# LSU_4_9_OpenAFR_Gauge.net
KiCad netlist of a schematic drawn in EAGLE
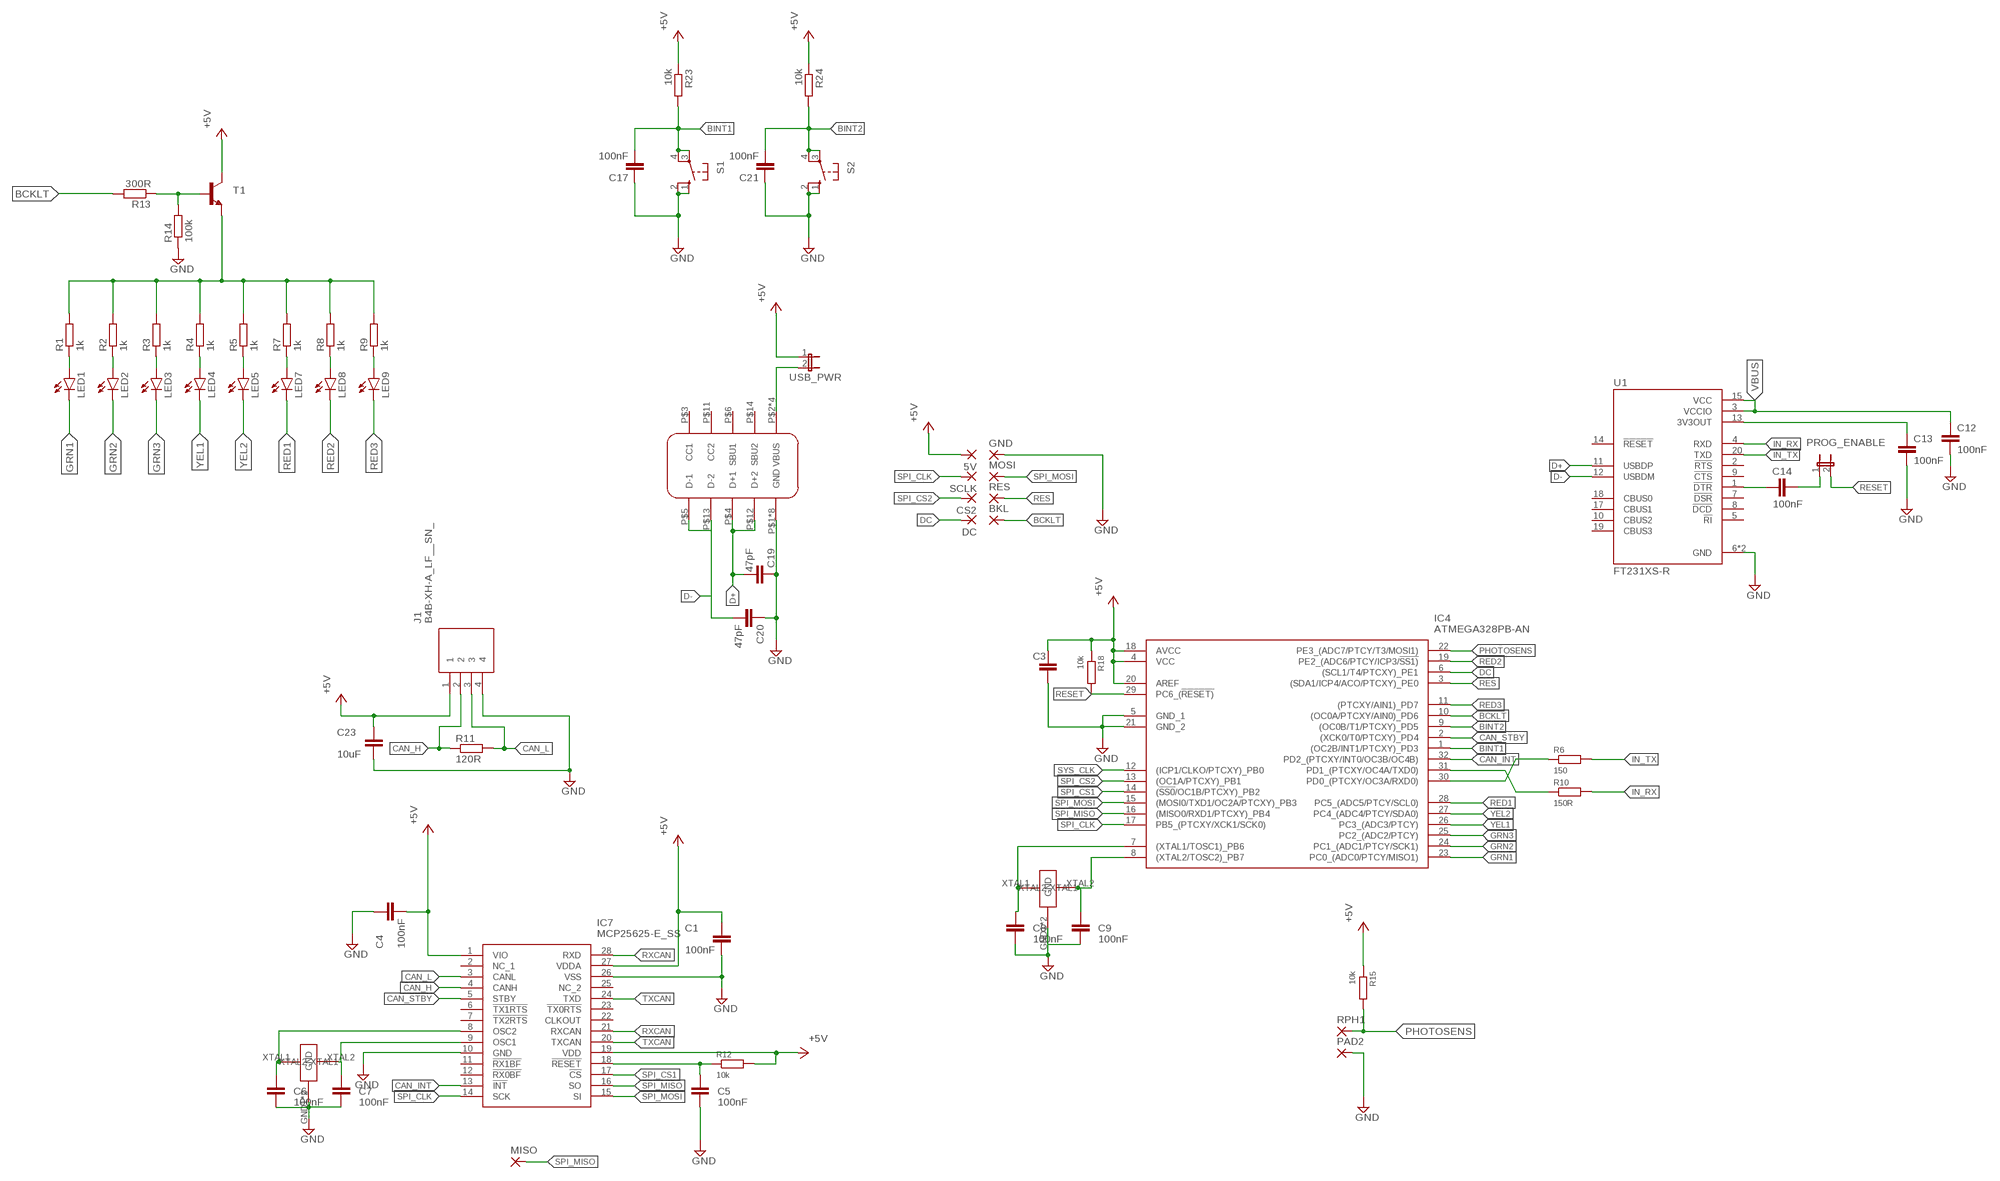
[diagram p0: schematic, sheet 1]

(export (version "E")
  (design (tool "Eeschema 10.0.6"))
  (components
    (comp (ref "5V")
      (value "1,6/0,9")
      (footprint "eagle-import:1,6_0,9")
      (libsource (lib "eagle-import") (part "1,6/0,9"))
    )
    (comp (ref "BKL")
      (value "1,6/0,9")
      (footprint "eagle-import:1,6_0,9")
      (libsource (lib "eagle-import") (part "1,6/0,9"))
    )
    (comp (ref "C1")
      (value "100nF")
      (footprint "eagle-import:C0805")
      (libsource (lib "eagle-import") (part "C-EUC0805"))
    )
    (comp (ref "C3")
      (value "100nF")
      (footprint "eagle-import:C0805")
      (libsource (lib "eagle-import") (part "C-EUC0805"))
    )
    (comp (ref "C4")
      (value "100nF")
      (footprint "eagle-import:C0805")
      (libsource (lib "eagle-import") (part "C-EUC0805"))
    )
    (comp (ref "C5")
      (value "100nF")
      (footprint "eagle-import:C0805")
      (libsource (lib "eagle-import") (part "C-EUC0805"))
    )
    (comp (ref "C6")
      (value "100nF")
      (footprint "eagle-import:C0805")
      (libsource (lib "eagle-import") (part "C-EUC0805"))
    )
    (comp (ref "C7")
      (value "100nF")
      (footprint "eagle-import:C0805")
      (libsource (lib "eagle-import") (part "C-EUC0805"))
    )
    (comp (ref "C8")
      (value "100nF")
      (footprint "eagle-import:C0805")
      (libsource (lib "eagle-import") (part "C-EUC0805"))
    )
    (comp (ref "C9")
      (value "100nF")
      (footprint "eagle-import:C0805")
      (libsource (lib "eagle-import") (part "C-EUC0805"))
    )
    (comp (ref "C12")
      (value "100nF")
      (footprint "eagle-import:C0805")
      (libsource (lib "eagle-import") (part "C-EUC0805"))
    )
    (comp (ref "C13")
      (value "100nF")
      (footprint "eagle-import:C0805")
      (libsource (lib "eagle-import") (part "C-EUC0805"))
    )
    (comp (ref "C14")
      (value "100nF")
      (footprint "eagle-import:C0805")
      (libsource (lib "eagle-import") (part "C-EUC0805"))
    )
    (comp (ref "C17")
      (value "100nF")
      (footprint "eagle-import:C0805")
      (libsource (lib "eagle-import") (part "C-EUC0805"))
    )
    (comp (ref "C19")
      (value "47pF")
      (footprint "eagle-import:C0805")
      (libsource (lib "eagle-import") (part "C-EUC0805"))
    )
    (comp (ref "C20")
      (value "47pF")
      (footprint "eagle-import:C0805")
      (libsource (lib "eagle-import") (part "C-EUC0805"))
    )
    (comp (ref "C21")
      (value "100nF")
      (footprint "eagle-import:C0805")
      (libsource (lib "eagle-import") (part "C-EUC0805"))
    )
    (comp (ref "C23")
      (value "10uF")
      (footprint "eagle-import:C0805")
      (libsource (lib "eagle-import") (part "C-EUC0805"))
    )
    (comp (ref "CS2")
      (value "1,6/0,9")
      (footprint "eagle-import:1,6_0,9")
      (libsource (lib "eagle-import") (part "1,6/0,9"))
    )
    (comp (ref "DC")
      (value "1,6/0,9")
      (footprint "eagle-import:1,6_0,9")
      (libsource (lib "eagle-import") (part "1,6/0,9"))
    )
    (comp (ref "GND")
      (value "1,6/0,9")
      (footprint "eagle-import:1,6_0,9")
      (libsource (lib "eagle-import") (part "1,6/0,9"))
    )
    (comp (ref "IC4")
      (value "ATMEGA328PB-AN")
      (footprint "eagle-import:QFP80P900X900X120-32N")
      (fields (field (name "MOUSER_PART_NUMBER") "556-ATMEGA328PB-AN"))
      (libsource (lib "eagle-import") (part "ATMEGA328PB-AN"))
    )
    (comp (ref "IC7")
      (value "MCP25625-E_SS")
      (footprint "eagle-import:SOP65P780X200-28N")
      (fields
        (field (name "MANUFACTURER_PART_NUMBER") "MCP25625-E/SS")
        (field (name "MOUSER_PART_NUMBER") "579-MCP25625-E/SS")
      )
      (libsource (lib "eagle-import") (part "MCP25625-E_SS"))
    )
    (comp (ref "J1")
      (value "B4B-XH-A_LF__SN_")
      (footprint "eagle-import:B4BXHALFSN")
      (fields
        (field (name "MANUFACTURER_PART_NUMBER") "B4B-XH-A(LF)(SN)")
        (field (name "MOUSER_PART_NUMBER") "306-B4BXHALFSN")
      )
      (libsource (lib "eagle-import") (part "B4B-XH-A_LF__SN_"))
    )
    (comp (ref "LED1")
      (value "LEDCHIPLED_1206")
      (footprint "eagle-import:CHIPLED_1206")
      (libsource (lib "eagle-import") (part "LEDCHIPLED_1206"))
    )
    (comp (ref "LED2")
      (value "LEDCHIPLED_1206")
      (footprint "eagle-import:CHIPLED_1206")
      (libsource (lib "eagle-import") (part "LEDCHIPLED_1206"))
    )
    (comp (ref "LED3")
      (value "LEDCHIPLED_1206")
      (footprint "eagle-import:CHIPLED_1206")
      (libsource (lib "eagle-import") (part "LEDCHIPLED_1206"))
    )
    (comp (ref "LED4")
      (value "LEDCHIPLED_1206")
      (footprint "eagle-import:CHIPLED_1206")
      (libsource (lib "eagle-import") (part "LEDCHIPLED_1206"))
    )
    (comp (ref "LED5")
      (value "LEDCHIPLED_1206")
      (footprint "eagle-import:CHIPLED_1206")
      (libsource (lib "eagle-import") (part "LEDCHIPLED_1206"))
    )
    (comp (ref "LED7")
      (value "LEDCHIPLED_1206")
      (footprint "eagle-import:CHIPLED_1206")
      (libsource (lib "eagle-import") (part "LEDCHIPLED_1206"))
    )
    (comp (ref "LED8")
      (value "LEDCHIPLED_1206")
      (footprint "eagle-import:CHIPLED_1206")
      (libsource (lib "eagle-import") (part "LEDCHIPLED_1206"))
    )
    (comp (ref "LED9")
      (value "LEDCHIPLED_1206")
      (footprint "eagle-import:CHIPLED_1206")
      (libsource (lib "eagle-import") (part "LEDCHIPLED_1206"))
    )
    (comp (ref "MISO")
      (value "1,6/0,9")
      (footprint "eagle-import:1,6_0,9")
      (libsource (lib "eagle-import") (part "1,6/0,9"))
    )
    (comp (ref "MOSI")
      (value "1,6/0,9")
      (footprint "eagle-import:1,6_0,9")
      (libsource (lib "eagle-import") (part "1,6/0,9"))
    )
    (comp (ref "PAD2")
      (value "1,6/0,8")
      (footprint "eagle-import:1,6_0,8")
      (libsource (lib "eagle-import") (part "1,6/0,8"))
    )
    (comp (ref "PROG_ENABLE")
      (value "JP1E")
      (footprint "eagle-import:JP1")
      (libsource (lib "eagle-import") (part "JP1E"))
    )
    (comp (ref "R1")
      (value "1k")
      (footprint "eagle-import:R0805")
      (libsource (lib "eagle-import") (part "R-EU_R0805"))
    )
    (comp (ref "R2")
      (value "1k")
      (footprint "eagle-import:R0805")
      (libsource (lib "eagle-import") (part "R-EU_R0805"))
    )
    (comp (ref "R3")
      (value "1k")
      (footprint "eagle-import:R0805")
      (libsource (lib "eagle-import") (part "R-EU_R0805"))
    )
    (comp (ref "R4")
      (value "1k")
      (footprint "eagle-import:R0805")
      (libsource (lib "eagle-import") (part "R-EU_R0805"))
    )
    (comp (ref "R5")
      (value "1k")
      (footprint "eagle-import:R0805")
      (libsource (lib "eagle-import") (part "R-EU_R0805"))
    )
    (comp (ref "R6")
      (value "150")
      (footprint "eagle-import:R0805")
      (libsource (lib "eagle-import") (part "R-EU_R0805"))
    )
    (comp (ref "R7")
      (value "1k")
      (footprint "eagle-import:R0805")
      (libsource (lib "eagle-import") (part "R-EU_R0805"))
    )
    (comp (ref "R8")
      (value "1k")
      (footprint "eagle-import:R0805")
      (libsource (lib "eagle-import") (part "R-EU_R0805"))
    )
    (comp (ref "R9")
      (value "1k")
      (footprint "eagle-import:R0805")
      (libsource (lib "eagle-import") (part "R-EU_R0805"))
    )
    (comp (ref "R10")
      (value "150R")
      (footprint "eagle-import:R0805")
      (libsource (lib "eagle-import") (part "R-EU_R0805"))
    )
    (comp (ref "R11")
      (value "120R")
      (footprint "eagle-import:R1206")
      (libsource (lib "eagle-import") (part "R-EU_R1206"))
    )
    (comp (ref "R12")
      (value "10k")
      (footprint "eagle-import:R0805")
      (libsource (lib "eagle-import") (part "R-EU_R0805"))
    )
    (comp (ref "R13")
      (value "300R")
      (footprint "eagle-import:R0805")
      (libsource (lib "eagle-import") (part "R-EU_R0805"))
    )
    (comp (ref "R14")
      (value "100k")
      (footprint "eagle-import:R0805")
      (libsource (lib "eagle-import") (part "R-EU_R0805"))
    )
    (comp (ref "R15")
      (value "10k")
      (footprint "eagle-import:R0805")
      (libsource (lib "eagle-import") (part "R-EU_R0805"))
    )
    (comp (ref "R18")
      (value "10k")
      (footprint "eagle-import:R0805")
      (libsource (lib "eagle-import") (part "R-EU_R0805"))
    )
    (comp (ref "R23")
      (value "10k")
      (footprint "eagle-import:R0805")
      (libsource (lib "eagle-import") (part "R-EU_R0805"))
    )
    (comp (ref "R24")
      (value "10k")
      (footprint "eagle-import:R0805")
      (libsource (lib "eagle-import") (part "R-EU_R0805"))
    )
    (comp (ref "RES")
      (value "1,6/0,9")
      (footprint "eagle-import:1,6_0,9")
      (libsource (lib "eagle-import") (part "1,6/0,9"))
    )
    (comp (ref "RPH1")
      (value "1,6/0,8")
      (footprint "eagle-import:1,6_0,8")
      (libsource (lib "eagle-import") (part "1,6/0,8"))
    )
    (comp (ref "S1")
      (value "10-XX")
      (footprint "eagle-import:B3F-10XX")
      (fields (field (name "MPN") "B3F-1000"))
      (libsource (lib "eagle-import") (part "10-XX"))
    )
    (comp (ref "S2")
      (value "10-XX")
      (footprint "eagle-import:B3F-10XX")
      (fields (field (name "MPN") "B3F-1000"))
      (libsource (lib "eagle-import") (part "10-XX"))
    )
    (comp (ref "SCLK")
      (value "1,6/0,9")
      (footprint "eagle-import:1,6_0,9")
      (libsource (lib "eagle-import") (part "1,6/0,9"))
    )
    (comp (ref "T1")
      (value "BC817-16-NPN-SOT23-BEC")
      (footprint "eagle-import:SOT23-BEC")
      (libsource (lib "eagle-import") (part "-NPN-SOT23-BECBC817-16"))
    )
    (comp (ref "U$1")
      (value "USBC-2.0-THT")
      (footprint "eagle-import:USBC-2.0-THT")
      (libsource (lib "eagle-import") (part "USBC-2.0-THT"))
    )
    (comp (ref "U$2")
      (value "E3X160181X04")
      (footprint "eagle-import:E3X160181X04")
      (libsource (lib "eagle-import") (part "E3X160181X04"))
    )
    (comp (ref "U$3")
      (value "E3X160181X04")
      (footprint "eagle-import:E3X160181X04")
      (libsource (lib "eagle-import") (part "E3X160181X04"))
    )
    (comp (ref "U1")
      (value "FT231XS-R")
      (footprint "eagle-import:SOP63P599X175-20N")
      (fields
        (field (name "DIGIKEY_PART_NUMBER") "768-1129-1-ND")
        (field (name "MF") "FTDI Chip")
        (field (name "MP") "FT231XSR")
      )
      (libsource (lib "eagle-import") (part "FT231XS-R"))
    )
    (comp (ref "USB_PWR")
      (value "JP1E")
      (footprint "eagle-import:JP1")
      (libsource (lib "eagle-import") (part "JP1E"))
    )
  )
  (nets
    (net (code "1") (name "+5V") (class "Default")
      (node (ref "5V") (pin "1") (pinfunction "P_1") (pintype "passive"))
      (node (ref "C1") (pin "1") (pinfunction "1_1") (pintype "passive"))
      (node (ref "C23") (pin "1") (pinfunction "1_1") (pintype "passive"))
      (node (ref "C3") (pin "1") (pinfunction "1_1") (pintype "passive"))
      (node (ref "C4") (pin "2") (pinfunction "2_2") (pintype "passive"))
      (node (ref "IC4") (pin "18") (pinfunction "AVCC_18") (pintype "bidirectional"))
      (node (ref "IC4") (pin "20") (pinfunction "AREF_20") (pintype "bidirectional"))
      (node (ref "IC4") (pin "4") (pinfunction "VCC_4") (pintype "bidirectional"))
      (node (ref "IC7") (pin "1") (pinfunction "VIO_1") (pintype "bidirectional"))
      (node (ref "IC7") (pin "19") (pinfunction "VDD_19") (pintype "bidirectional"))
      (node (ref "IC7") (pin "27") (pinfunction "VDDA_27") (pintype "bidirectional"))
      (node (ref "J1") (pin "1") (pinfunction "1_1") (pintype "bidirectional"))
      (node (ref "R12") (pin "2") (pinfunction "2_2") (pintype "passive"))
      (node (ref "R15") (pin "1") (pinfunction "1_1") (pintype "passive"))
      (node (ref "R18") (pin "1") (pinfunction "1_1") (pintype "passive"))
      (node (ref "R23") (pin "1") (pinfunction "1_1") (pintype "passive"))
      (node (ref "R24") (pin "1") (pinfunction "1_1") (pintype "passive"))
      (node (ref "T1") (pin "C") (pinfunction "C_C") (pintype "passive"))
      (node (ref "USB_PWR") (pin "1") (pinfunction "1_1") (pintype "passive"))
    )
    (net (code "2") (name "BCKLT") (class "Default")
      (node (ref "BKL") (pin "1") (pinfunction "P_1") (pintype "passive"))
      (node (ref "IC4") (pin "10") (pinfunction "(OC0A/PTCXY/AIN0)_PD6_10") (pintype "bidirectional"))
      (node (ref "R13") (pin "2") (pinfunction "2_2") (pintype "passive"))
    )
    (net (code "3") (name "BINT1") (class "Default")
      (node (ref "C17") (pin "2") (pinfunction "2_2") (pintype "passive"))
      (node (ref "IC4") (pin "1") (pinfunction "(OC2B/INT1/PTCXY)_PD3_1") (pintype "bidirectional"))
      (node (ref "R23") (pin "2") (pinfunction "2_2") (pintype "passive"))
      (node (ref "S1") (pin "3") (pinfunction "P_3") (pintype "passive"))
      (node (ref "S1") (pin "4") (pinfunction "P1_4") (pintype "passive"))
    )
    (net (code "4") (name "BINT2") (class "Default")
      (node (ref "C21") (pin "2") (pinfunction "2_2") (pintype "passive"))
      (node (ref "IC4") (pin "9") (pinfunction "(OC0B/T1/PTCXY)_PD5_9") (pintype "bidirectional"))
      (node (ref "R24") (pin "2") (pinfunction "2_2") (pintype "passive"))
      (node (ref "S2") (pin "3") (pinfunction "P_3") (pintype "passive"))
      (node (ref "S2") (pin "4") (pinfunction "P1_4") (pintype "passive"))
    )
    (net (code "5") (name "CAN_H") (class "Default")
      (node (ref "IC7") (pin "4") (pinfunction "CANH_4") (pintype "bidirectional"))
      (node (ref "J1") (pin "2") (pinfunction "2_2") (pintype "bidirectional"))
      (node (ref "R11") (pin "1") (pinfunction "1_1") (pintype "passive"))
    )
    (net (code "6") (name "CAN_INT") (class "Default")
      (node (ref "IC4") (pin "32") (pinfunction "PD2_(PTCXY/INT0/OC3B/OC4B)_32") (pintype "bidirectional"))
      (node (ref "IC7") (pin "13") (pinfunction "~{INT}_13") (pintype "bidirectional"))
    )
    (net (code "7") (name "CAN_L") (class "Default")
      (node (ref "IC7") (pin "3") (pinfunction "CANL_3") (pintype "bidirectional"))
      (node (ref "J1") (pin "3") (pinfunction "3_3") (pintype "bidirectional"))
      (node (ref "R11") (pin "2") (pinfunction "2_2") (pintype "passive"))
    )
    (net (code "8") (name "CAN_STBY") (class "Default")
      (node (ref "IC4") (pin "2") (pinfunction "(XCK0/T0/PTCXY)_PD4_2") (pintype "bidirectional"))
      (node (ref "IC7") (pin "5") (pinfunction "STBY_5") (pintype "bidirectional"))
    )
    (net (code "9") (name "D+") (class "Default")
      (node (ref "C19") (pin "2") (pinfunction "2_2") (pintype "passive"))
      (node (ref "U$1") (pin "P$12") (pinfunction "D+2_P$12") (pintype "bidirectional"))
      (node (ref "U$1") (pin "P$4") (pinfunction "D+1_P$4") (pintype "bidirectional"))
      (node (ref "U1") (pin "11") (pinfunction "USBDP_11") (pintype "input"))
    )
    (net (code "10") (name "D-") (class "Default")
      (node (ref "C20") (pin "2") (pinfunction "2_2") (pintype "passive"))
      (node (ref "U$1") (pin "P$13") (pinfunction "D-2_P$13") (pintype "bidirectional"))
      (node (ref "U$1") (pin "P$5") (pinfunction "D-1_P$5") (pintype "bidirectional"))
      (node (ref "U1") (pin "12") (pinfunction "USBDM_12") (pintype "input"))
    )
    (net (code "11") (name "DC") (class "Default")
      (node (ref "DC") (pin "1") (pinfunction "P_1") (pintype "passive"))
      (node (ref "IC4") (pin "6") (pinfunction "(SCL1/T4/PTCXY)_PE1_6") (pintype "bidirectional"))
    )
    (net (code "12") (name "GND") (class "Default")
      (node (ref "C1") (pin "2") (pinfunction "2_2") (pintype "passive"))
      (node (ref "C12") (pin "2") (pinfunction "2_2") (pintype "passive"))
      (node (ref "C13") (pin "2") (pinfunction "2_2") (pintype "passive"))
      (node (ref "C17") (pin "1") (pinfunction "1_1") (pintype "passive"))
      (node (ref "C19") (pin "1") (pinfunction "1_1") (pintype "passive"))
      (node (ref "C20") (pin "1") (pinfunction "1_1") (pintype "passive"))
      (node (ref "C21") (pin "1") (pinfunction "1_1") (pintype "passive"))
      (node (ref "C23") (pin "2") (pinfunction "2_2") (pintype "passive"))
      (node (ref "C3") (pin "2") (pinfunction "2_2") (pintype "passive"))
      (node (ref "C4") (pin "1") (pinfunction "1_1") (pintype "passive"))
      (node (ref "C5") (pin "2") (pinfunction "2_2") (pintype "passive"))
      (node (ref "C6") (pin "2") (pinfunction "2_2") (pintype "passive"))
      (node (ref "C7") (pin "2") (pinfunction "2_2") (pintype "passive"))
      (node (ref "C8") (pin "2") (pinfunction "2_2") (pintype "passive"))
      (node (ref "C9") (pin "2") (pinfunction "2_2") (pintype "passive"))
      (node (ref "GND") (pin "1") (pinfunction "P_1") (pintype "passive"))
      (node (ref "IC4") (pin "21") (pinfunction "GND_2_21") (pintype "bidirectional"))
      (node (ref "IC4") (pin "5") (pinfunction "GND_1_5") (pintype "bidirectional"))
      (node (ref "IC7") (pin "10") (pinfunction "GND_10") (pintype "bidirectional"))
      (node (ref "IC7") (pin "26") (pinfunction "VSS_26") (pintype "bidirectional"))
      (node (ref "J1") (pin "4") (pinfunction "4_4") (pintype "bidirectional"))
      (node (ref "PAD2") (pin "1") (pinfunction "P_1") (pintype "passive"))
      (node (ref "R14") (pin "1") (pinfunction "1_1") (pintype "passive"))
      (node (ref "S1") (pin "1") (pinfunction "S_1") (pintype "passive"))
      (node (ref "S1") (pin "2") (pinfunction "S1_2") (pintype "passive"))
      (node (ref "S2") (pin "1") (pinfunction "S_1") (pintype "passive"))
      (node (ref "S2") (pin "2") (pinfunction "S1_2") (pintype "passive"))
      (node (ref "U$1") (pin "P$1") (pinfunction "GND_P$1") (pintype "bidirectional"))
      (node (ref "U$1") (pin "P$16") (pinfunction "GND_P$16") (pintype "bidirectional"))
      (node (ref "U$1") (pin "P$17") (pinfunction "GND_P$17") (pintype "bidirectional"))
      (node (ref "U$1") (pin "P$18") (pinfunction "GND_P$18") (pintype "bidirectional"))
      (node (ref "U$1") (pin "P$19") (pinfunction "GND_P$19") (pintype "bidirectional"))
      (node (ref "U$1") (pin "P$20") (pinfunction "GND_P$20") (pintype "bidirectional"))
      (node (ref "U$1") (pin "P$8") (pinfunction "GND_P$8") (pintype "bidirectional"))
      (node (ref "U$1") (pin "P$9") (pinfunction "GND_P$9") (pintype "bidirectional"))
      (node (ref "U$2") (pin "GND1") (pinfunction "GND_GND1") (pintype "bidirectional"))
      (node (ref "U$2") (pin "GND2") (pinfunction "GND_GND2") (pintype "bidirectional"))
      (node (ref "U$3") (pin "GND1") (pinfunction "GND_GND1") (pintype "bidirectional"))
      (node (ref "U$3") (pin "GND2") (pinfunction "GND_GND2") (pintype "bidirectional"))
      (node (ref "U1") (pin "16") (pinfunction "GND_16") (pintype "power_in"))
      (node (ref "U1") (pin "6") (pinfunction "GND_6") (pintype "power_in"))
    )
    (net (code "13") (name "GRN1") (class "Default")
      (node (ref "IC4") (pin "23") (pinfunction "PC0_(ADC0/PTCY/MISO1)_23") (pintype "bidirectional"))
      (node (ref "LED1") (pin "C") (pinfunction "C_C") (pintype "passive"))
    )
    (net (code "14") (name "GRN2") (class "Default")
      (node (ref "IC4") (pin "24") (pinfunction "PC1_(ADC1/PTCY/SCK1)_24") (pintype "bidirectional"))
      (node (ref "LED2") (pin "C") (pinfunction "C_C") (pintype "passive"))
    )
    (net (code "15") (name "GRN3") (class "Default")
      (node (ref "IC4") (pin "25") (pinfunction "PC2_(ADC2/PTCY)_25") (pintype "bidirectional"))
      (node (ref "LED3") (pin "C") (pinfunction "C_C") (pintype "passive"))
    )
    (net (code "16") (name "IN_RX") (class "Default")
      (node (ref "R10") (pin "2") (pinfunction "2_2") (pintype "passive"))
      (node (ref "U1") (pin "4") (pinfunction "RXD_4") (pintype "input"))
    )
    (net (code "17") (name "IN_TX") (class "Default")
      (node (ref "R6") (pin "2") (pinfunction "2_2") (pintype "passive"))
      (node (ref "U1") (pin "20") (pinfunction "TXD_20") (pintype "output"))
    )
    (net (code "18") (name "Net-(C14-Pad2)") (class "Default")
      (node (ref "C14") (pin "2") (pinfunction "2_2") (pintype "passive"))
      (node (ref "PROG_ENABLE") (pin "1") (pinfunction "1_1") (pintype "passive"))
    )
    (net (code "19") (name "Net-(IC4-(XTAL1{slash}TOSC1)_PB6)") (class "Default")
      (node (ref "C8") (pin "1") (pinfunction "1_1") (pintype "passive"))
      (node (ref "IC4") (pin "7") (pinfunction "(XTAL1/TOSC1)_PB6_7") (pintype "bidirectional"))
      (node (ref "U$3") (pin "XTAL1") (pinfunction "XTAL1_XTAL1") (pintype "bidirectional"))
    )
    (net (code "20") (name "Net-(IC4-(XTAL2{slash}TOSC2)_PB7)") (class "Default")
      (node (ref "C9") (pin "1") (pinfunction "1_1") (pintype "passive"))
      (node (ref "IC4") (pin "8") (pinfunction "(XTAL2/TOSC2)_PB7_8") (pintype "bidirectional"))
      (node (ref "U$3") (pin "XTAL2") (pinfunction "XTAL2_XTAL2") (pintype "bidirectional"))
    )
    (net (code "21") (name "Net-(IC4-PD0_(PTCXY{slash}OC3A{slash}RXD0))") (class "Default")
      (node (ref "IC4") (pin "30") (pinfunction "PD0_(PTCXY/OC3A/RXD0)_30") (pintype "bidirectional"))
      (node (ref "R6") (pin "1") (pinfunction "1_1") (pintype "passive"))
    )
    (net (code "22") (name "Net-(IC4-PD1_(PTCXY{slash}OC4A{slash}TXD0))") (class "Default")
      (node (ref "IC4") (pin "31") (pinfunction "PD1_(PTCXY/OC4A/TXD0)_31") (pintype "bidirectional"))
      (node (ref "R10") (pin "1") (pinfunction "1_1") (pintype "passive"))
    )
    (net (code "23") (name "Net-(IC7-OSC1)") (class "Default")
      (node (ref "C7") (pin "1") (pinfunction "1_1") (pintype "passive"))
      (node (ref "IC7") (pin "9") (pinfunction "OSC1_9") (pintype "bidirectional"))
      (node (ref "U$2") (pin "XTAL2") (pinfunction "XTAL2_XTAL2") (pintype "bidirectional"))
    )
    (net (code "24") (name "Net-(IC7-OSC2)") (class "Default")
      (node (ref "C6") (pin "1") (pinfunction "1_1") (pintype "passive"))
      (node (ref "IC7") (pin "8") (pinfunction "OSC2_8") (pintype "bidirectional"))
      (node (ref "U$2") (pin "XTAL1") (pinfunction "XTAL1_XTAL1") (pintype "bidirectional"))
    )
    (net (code "25") (name "Net-(IC7-~{RESET})") (class "Default")
      (node (ref "C5") (pin "1") (pinfunction "1_1") (pintype "passive"))
      (node (ref "IC7") (pin "18") (pinfunction "~{RESET}_18") (pintype "bidirectional"))
      (node (ref "R12") (pin "1") (pinfunction "1_1") (pintype "passive"))
    )
    (net (code "26") (name "Net-(LED1-PadA)") (class "Default")
      (node (ref "LED1") (pin "A") (pinfunction "A_A") (pintype "passive"))
      (node (ref "R1") (pin "1") (pinfunction "1_1") (pintype "passive"))
    )
    (net (code "27") (name "Net-(LED2-PadA)") (class "Default")
      (node (ref "LED2") (pin "A") (pinfunction "A_A") (pintype "passive"))
      (node (ref "R2") (pin "1") (pinfunction "1_1") (pintype "passive"))
    )
    (net (code "28") (name "Net-(LED3-PadA)") (class "Default")
      (node (ref "LED3") (pin "A") (pinfunction "A_A") (pintype "passive"))
      (node (ref "R3") (pin "1") (pinfunction "1_1") (pintype "passive"))
    )
    (net (code "29") (name "Net-(LED4-PadA)") (class "Default")
      (node (ref "LED4") (pin "A") (pinfunction "A_A") (pintype "passive"))
      (node (ref "R4") (pin "1") (pinfunction "1_1") (pintype "passive"))
    )
    (net (code "30") (name "Net-(LED5-PadA)") (class "Default")
      (node (ref "LED5") (pin "A") (pinfunction "A_A") (pintype "passive"))
      (node (ref "R5") (pin "1") (pinfunction "1_1") (pintype "passive"))
    )
    (net (code "31") (name "Net-(LED7-PadA)") (class "Default")
      (node (ref "LED7") (pin "A") (pinfunction "A_A") (pintype "passive"))
      (node (ref "R7") (pin "1") (pinfunction "1_1") (pintype "passive"))
    )
    (net (code "32") (name "Net-(LED8-PadA)") (class "Default")
      (node (ref "LED8") (pin "A") (pinfunction "A_A") (pintype "passive"))
      (node (ref "R8") (pin "1") (pinfunction "1_1") (pintype "passive"))
    )
    (net (code "33") (name "Net-(LED9-PadA)") (class "Default")
      (node (ref "LED9") (pin "A") (pinfunction "A_A") (pintype "passive"))
      (node (ref "R9") (pin "1") (pinfunction "1_1") (pintype "passive"))
    )
    (net (code "34") (name "Net-(R1-Pad2)") (class "Default")
      (node (ref "R1") (pin "2") (pinfunction "2_2") (pintype "passive"))
      (node (ref "R2") (pin "2") (pinfunction "2_2") (pintype "passive"))
      (node (ref "R3") (pin "2") (pinfunction "2_2") (pintype "passive"))
      (node (ref "R4") (pin "2") (pinfunction "2_2") (pintype "passive"))
      (node (ref "R5") (pin "2") (pinfunction "2_2") (pintype "passive"))
      (node (ref "R7") (pin "2") (pinfunction "2_2") (pintype "passive"))
      (node (ref "R8") (pin "2") (pinfunction "2_2") (pintype "passive"))
      (node (ref "R9") (pin "2") (pinfunction "2_2") (pintype "passive"))
      (node (ref "T1") (pin "E") (pinfunction "E_E") (pintype "passive"))
    )
    (net (code "35") (name "Net-(R13-Pad1)") (class "Default")
      (node (ref "R13") (pin "1") (pinfunction "1_1") (pintype "passive"))
      (node (ref "R14") (pin "2") (pinfunction "2_2") (pintype "passive"))
      (node (ref "T1") (pin "B") (pinfunction "B_B") (pintype "passive"))
    )
    (net (code "36") (name "Net-(U1-3V3OUT)") (class "Default")
      (node (ref "C13") (pin "1") (pinfunction "1_1") (pintype "passive"))
      (node (ref "U1") (pin "13") (pinfunction "3V3OUT_13") (pintype "power_in"))
    )
    (net (code "37") (name "Net-(U1-~{DTR})") (class "Default")
      (node (ref "C14") (pin "1") (pinfunction "1_1") (pintype "passive"))
      (node (ref "U1") (pin "1") (pinfunction "~{DTR}_1") (pintype "output"))
    )
    (net (code "38") (name "PHOTOSENS") (class "Default")
      (node (ref "IC4") (pin "22") (pinfunction "PE3_(ADC7/PTCY/T3/MOSI1)_22") (pintype "bidirectional"))
      (node (ref "R15") (pin "2") (pinfunction "2_2") (pintype "passive"))
      (node (ref "RPH1") (pin "1") (pinfunction "P_1") (pintype "passive"))
    )
    (net (code "39") (name "RED1") (class "Default")
      (node (ref "IC4") (pin "28") (pinfunction "PC5_(ADC5/PTCY/SCL0)_28") (pintype "bidirectional"))
      (node (ref "LED7") (pin "C") (pinfunction "C_C") (pintype "passive"))
    )
    (net (code "40") (name "RED2") (class "Default")
      (node (ref "IC4") (pin "19") (pinfunction "PE2_(ADC6/PTCY/ICP3/~{SS1})_19") (pintype "bidirectional"))
      (node (ref "LED8") (pin "C") (pinfunction "C_C") (pintype "passive"))
    )
    (net (code "41") (name "RED3") (class "Default")
      (node (ref "IC4") (pin "11") (pinfunction "(PTCXY/AIN1)_PD7_11") (pintype "bidirectional"))
      (node (ref "LED9") (pin "C") (pinfunction "C_C") (pintype "passive"))
    )
    (net (code "42") (name "RES") (class "Default")
      (node (ref "IC4") (pin "3") (pinfunction "(SDA1/ICP4/ACO/PTCXY)_PE0_3") (pintype "bidirectional"))
      (node (ref "RES") (pin "1") (pinfunction "P_1") (pintype "passive"))
    )
    (net (code "43") (name "RESET") (class "Default")
      (node (ref "IC4") (pin "29") (pinfunction "PC6_(~{RESET})_29") (pintype "bidirectional"))
      (node (ref "PROG_ENABLE") (pin "2") (pinfunction "2_2") (pintype "passive"))
      (node (ref "R18") (pin "2") (pinfunction "2_2") (pintype "passive"))
    )
    (net (code "44") (name "RXCAN") (class "Default")
      (node (ref "IC7") (pin "21") (pinfunction "RXCAN_21") (pintype "bidirectional"))
      (node (ref "IC7") (pin "28") (pinfunction "RXD_28") (pintype "bidirectional"))
    )
    (net (code "45") (name "SPI_CLK") (class "Default")
      (node (ref "IC4") (pin "17") (pinfunction "PB5_(PTCXY/XCK1/SCK0)_17") (pintype "bidirectional"))
      (node (ref "IC7") (pin "14") (pinfunction "SCK_14") (pintype "bidirectional"))
      (node (ref "SCLK") (pin "1") (pinfunction "P_1") (pintype "passive"))
    )
    (net (code "46") (name "SPI_CS1") (class "Default")
      (node (ref "IC4") (pin "14") (pinfunction "(~{SS0}/OC1B/PTCXY)_PB2_14") (pintype "bidirectional"))
      (node (ref "IC7") (pin "17") (pinfunction "~{CS}_17") (pintype "bidirectional"))
    )
    (net (code "47") (name "SPI_CS2") (class "Default")
      (node (ref "CS2") (pin "1") (pinfunction "P_1") (pintype "passive"))
      (node (ref "IC4") (pin "13") (pinfunction "(OC1A/PTCXY)_PB1_13") (pintype "bidirectional"))
    )
    (net (code "48") (name "SPI_MISO") (class "Default")
      (node (ref "IC4") (pin "16") (pinfunction "(MISO0/RXD1/PTCXY)_PB4_16") (pintype "bidirectional"))
      (node (ref "IC7") (pin "16") (pinfunction "SO_16") (pintype "bidirectional"))
      (node (ref "MISO") (pin "1") (pinfunction "P_1") (pintype "passive"))
    )
    (net (code "49") (name "SPI_MOSI") (class "Default")
      (node (ref "IC4") (pin "15") (pinfunction "(MOSI0/TXD1/OC2A/PTCXY)_PB3_15") (pintype "bidirectional"))
      (node (ref "IC7") (pin "15") (pinfunction "SI_15") (pintype "bidirectional"))
      (node (ref "MOSI") (pin "1") (pinfunction "P_1") (pintype "passive"))
    )
    (net (code "50") (name "SYS_CLK") (class "Default")
      (node (ref "IC4") (pin "12") (pinfunction "(ICP1/CLKO/PTCXY)_PB0_12") (pintype "bidirectional"))
    )
    (net (code "51") (name "TXCAN") (class "Default")
      (node (ref "IC7") (pin "20") (pinfunction "TXCAN_20") (pintype "bidirectional"))
      (node (ref "IC7") (pin "24") (pinfunction "TXD_24") (pintype "bidirectional"))
    )
    (net (code "52") (name "VBUS") (class "Default")
      (node (ref "C12") (pin "1") (pinfunction "1_1") (pintype "passive"))
      (node (ref "U$1") (pin "P$10") (pinfunction "VBUS_P$10") (pintype "bidirectional"))
      (node (ref "U$1") (pin "P$15") (pinfunction "VBUS_P$15") (pintype "bidirectional"))
      (node (ref "U$1") (pin "P$2") (pinfunction "VBUS_P$2") (pintype "bidirectional"))
      (node (ref "U$1") (pin "P$7") (pinfunction "VBUS_P$7") (pintype "bidirectional"))
      (node (ref "U1") (pin "15") (pinfunction "VCC_15") (pintype "power_in"))
      (node (ref "U1") (pin "3") (pinfunction "VCCIO_3") (pintype "power_in"))
      (node (ref "USB_PWR") (pin "2") (pinfunction "2_2") (pintype "passive"))
    )
    (net (code "53") (name "YEL1") (class "Default")
      (node (ref "IC4") (pin "26") (pinfunction "PC3_(ADC3/PTCY)_26") (pintype "bidirectional"))
      (node (ref "LED4") (pin "C") (pinfunction "C_C") (pintype "passive"))
    )
    (net (code "54") (name "YEL2") (class "Default")
      (node (ref "IC4") (pin "27") (pinfunction "PC4_(ADC4/PTCY/SDA0)_27") (pintype "bidirectional"))
      (node (ref "LED5") (pin "C") (pinfunction "C_C") (pintype "passive"))
    )
    (net (code "55") (name "unconnected-(IC7-CLKOUT-Pad22)") (class "Default")
      (node (ref "IC7") (pin "22") (pinfunction "CLKOUT_22") (pintype "bidirectional"))
    )
    (net (code "56") (name "unconnected-(IC7-NC_1-Pad2)") (class "Default")
      (node (ref "IC7") (pin "2") (pinfunction "NC_1_2") (pintype "bidirectional"))
    )
    (net (code "57") (name "unconnected-(IC7-NC_2-Pad25)") (class "Default")
      (node (ref "IC7") (pin "25") (pinfunction "NC_2_25") (pintype "bidirectional"))
    )
    (net (code "58") (name "unconnected-(IC7-~{RX0BF}-Pad12)") (class "Default")
      (node (ref "IC7") (pin "12") (pinfunction "~{RX0BF}_12") (pintype "bidirectional"))
    )
    (net (code "59") (name "unconnected-(IC7-~{RX1BF}-Pad11)") (class "Default")
      (node (ref "IC7") (pin "11") (pinfunction "~{RX1BF}_11") (pintype "bidirectional"))
    )
    (net (code "60") (name "unconnected-(IC7-~{TX0RTS}-Pad23)") (class "Default")
      (node (ref "IC7") (pin "23") (pinfunction "~{TX0RTS}_23") (pintype "bidirectional"))
    )
    (net (code "61") (name "unconnected-(IC7-~{TX1RTS}-Pad6)") (class "Default")
      (node (ref "IC7") (pin "6") (pinfunction "~{TX1RTS}_6") (pintype "bidirectional"))
    )
    (net (code "62") (name "unconnected-(IC7-~{TX2RTS}-Pad7)") (class "Default")
      (node (ref "IC7") (pin "7") (pinfunction "~{TX2RTS}_7") (pintype "bidirectional"))
    )
    (net (code "63") (name "unconnected-(U$1-CC1-PadP$3)") (class "Default")
      (node (ref "U$1") (pin "P$3") (pinfunction "CC1_P$3") (pintype "bidirectional"))
    )
    (net (code "64") (name "unconnected-(U$1-CC2-PadP$11)") (class "Default")
      (node (ref "U$1") (pin "P$11") (pinfunction "CC2_P$11") (pintype "bidirectional"))
    )
    (net (code "65") (name "unconnected-(U$1-SBU1-PadP$6)") (class "Default")
      (node (ref "U$1") (pin "P$6") (pinfunction "SBU1_P$6") (pintype "bidirectional"))
    )
    (net (code "66") (name "unconnected-(U$1-SBU2-PadP$14)") (class "Default")
      (node (ref "U$1") (pin "P$14") (pinfunction "SBU2_P$14") (pintype "bidirectional"))
    )
    (net (code "67") (name "unconnected-(U1-CBUS0-Pad18)") (class "Default")
      (node (ref "U1") (pin "18") (pinfunction "CBUS0_18") (pintype "bidirectional"))
    )
    (net (code "68") (name "unconnected-(U1-CBUS1-Pad17)") (class "Default")
      (node (ref "U1") (pin "17") (pinfunction "CBUS1_17") (pintype "bidirectional"))
    )
    (net (code "69") (name "unconnected-(U1-CBUS2-Pad10)") (class "Default")
      (node (ref "U1") (pin "10") (pinfunction "CBUS2_10") (pintype "bidirectional"))
    )
    (net (code "70") (name "unconnected-(U1-CBUS3-Pad19)") (class "Default")
      (node (ref "U1") (pin "19") (pinfunction "CBUS3_19") (pintype "bidirectional"))
    )
    (net (code "71") (name "unconnected-(U1-~{CTS}-Pad9)") (class "Default")
      (node (ref "U1") (pin "9") (pinfunction "~{CTS}_9") (pintype "input"))
    )
    (net (code "72") (name "unconnected-(U1-~{DCD}-Pad8)") (class "Default")
      (node (ref "U1") (pin "8") (pinfunction "~{DCD}_8") (pintype "input"))
    )
    (net (code "73") (name "unconnected-(U1-~{DSR}-Pad7)") (class "Default")
      (node (ref "U1") (pin "7") (pinfunction "~{DSR}_7") (pintype "input"))
    )
    (net (code "74") (name "unconnected-(U1-~{RESET}-Pad14)") (class "Default")
      (node (ref "U1") (pin "14") (pinfunction "~{RESET}_14") (pintype "input"))
    )
    (net (code "75") (name "unconnected-(U1-~{RI}-Pad5)") (class "Default")
      (node (ref "U1") (pin "5") (pinfunction "~{RI}_5") (pintype "input"))
    )
    (net (code "76") (name "unconnected-(U1-~{RTS}-Pad2)") (class "Default")
      (node (ref "U1") (pin "2") (pinfunction "~{RTS}_2") (pintype "output"))
    )
  )
)
